# dimmer_for_poor.net
KiCad netlist of a schematic drawn in EAGLE
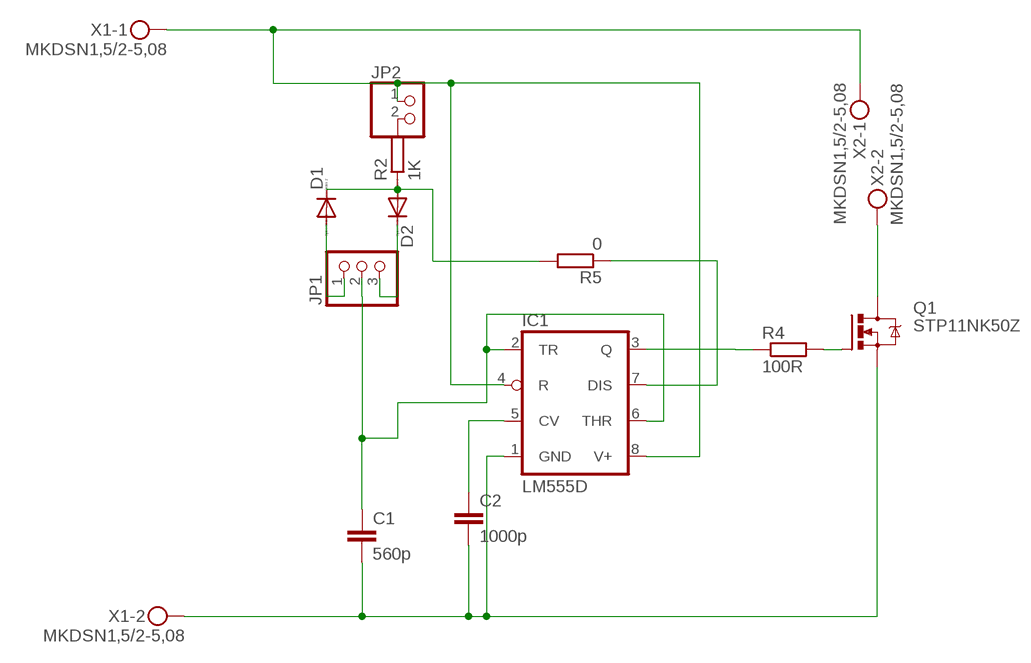
[diagram p0: schematic, sheet 1]

(export (version "E")
  (design (tool "Eeschema 10.0.6"))
  (components
    (comp (ref "C1")
      (value "560p")
      (footprint "eagle-import:C0805")
      (libsource (lib "eagle-import") (part "C-EUC0805"))
    )
    (comp (ref "C2")
      (value "1000p")
      (footprint "eagle-import:C1206")
      (libsource (lib "eagle-import") (part "C-EUC1206"))
    )
    (comp (ref "D1")
      (value "DIODE-MINIMELF")
      (footprint "eagle-import:MINIMELF")
      (libsource (lib "eagle-import") (part "DIODE-MINIMELF"))
    )
    (comp (ref "D2")
      (value "DIODE-MINIMELF")
      (footprint "eagle-import:MINIMELF")
      (libsource (lib "eagle-import") (part "DIODE-MINIMELF"))
    )
    (comp (ref "IC1")
      (value "LM555D")
      (footprint "eagle-import:SO08")
      (libsource (lib "eagle-import") (part "555DLM"))
    )
    (comp (ref "JP1")
      (value "PINHD-1X3/90")
      (footprint "eagle-import:1X03_90")
      (libsource (lib "eagle-import") (part "PINHD-1X3/90"))
    )
    (comp (ref "JP2")
      (value "PINHD-1X2")
      (footprint "eagle-import:1X02")
      (libsource (lib "eagle-import") (part "PINHD-1X2"))
    )
    (comp (ref "Q1")
      (value "STP11NK50Z")
      (footprint "eagle-import:TO220BV")
      (libsource (lib "eagle-import") (part "IRF740"))
    )
    (comp (ref "R2")
      (value "1K")
      (footprint "eagle-import:R0603")
      (libsource (lib "eagle-import") (part "R-EU_R0603"))
    )
    (comp (ref "R4")
      (value "100R")
      (footprint "eagle-import:R1206")
      (libsource (lib "eagle-import") (part "R-EU_R1206"))
    )
    (comp (ref "R5")
      (value "0")
      (footprint "eagle-import:R1206")
      (libsource (lib "eagle-import") (part "R-EU_R1206"))
    )
    (comp (ref "X1")
      (value "MKDSN1,5/2-5,08")
      (footprint "eagle-import:MKDSN1,5_2-5,08")
      (libsource (lib "eagle-import") (part "MKDSN1,5/2-5,08"))
    )
    (comp (ref "X2")
      (value "MKDSN1,5/2-5,08")
      (footprint "eagle-import:MKDSN1,5_2-5,08")
      (libsource (lib "eagle-import") (part "MKDSN1,5/2-5,08"))
    )
  )
  (nets
    (net (code "1") (name "Net-(D1-PadA)") (class "Default")
      (node (ref "D1") (pin "A") (pinfunction "A_A") (pintype "passive"))
      (node (ref "JP1") (pin "1") (pinfunction "1_1") (pintype "passive"))
    )
    (net (code "2") (name "Net-(D1-PadC)") (class "Default")
      (node (ref "D1") (pin "C") (pinfunction "C_C") (pintype "passive"))
      (node (ref "D2") (pin "A") (pinfunction "A_A") (pintype "passive"))
      (node (ref "R2") (pin "1") (pinfunction "1_1") (pintype "passive"))
      (node (ref "R5") (pin "2") (pinfunction "2_2") (pintype "passive"))
    )
    (net (code "3") (name "Net-(D2-PadC)") (class "Default")
      (node (ref "D2") (pin "C") (pinfunction "C_C") (pintype "passive"))
      (node (ref "JP1") (pin "3") (pinfunction "3_3") (pintype "passive"))
    )
    (net (code "4") (name "Net-(IC1-CV)") (class "Default")
      (node (ref "C2") (pin "1") (pinfunction "1_1") (pintype "passive"))
      (node (ref "IC1") (pin "5") (pinfunction "CV_5") (pintype "input"))
    )
    (net (code "5") (name "Net-(IC1-DIS)") (class "Default")
      (node (ref "IC1") (pin "7") (pinfunction "DIS_7") (pintype "input"))
      (node (ref "R5") (pin "1") (pinfunction "1_1") (pintype "passive"))
    )
    (net (code "6") (name "Net-(IC1-GND)") (class "Default")
      (node (ref "C1") (pin "2") (pinfunction "2_2") (pintype "passive"))
      (node (ref "C2") (pin "2") (pinfunction "2_2") (pintype "passive"))
      (node (ref "IC1") (pin "1") (pinfunction "GND_1") (pintype "power_in"))
      (node (ref "Q1") (pin "S") (pinfunction "S_S") (pintype "passive"))
      (node (ref "X1") (pin "2") (pinfunction "KL_2") (pintype "passive"))
    )
    (net (code "7") (name "Net-(IC1-Q)") (class "Default")
      (node (ref "IC1") (pin "3") (pinfunction "Q_3") (pintype "output"))
      (node (ref "R4") (pin "1") (pinfunction "1_1") (pintype "passive"))
    )
    (net (code "8") (name "Net-(IC1-R)") (class "Default")
      (node (ref "IC1") (pin "4") (pinfunction "R_4") (pintype "input"))
      (node (ref "IC1") (pin "8") (pinfunction "V+_8") (pintype "power_in"))
      (node (ref "JP2") (pin "1") (pinfunction "1_1") (pintype "passive"))
      (node (ref "X1") (pin "1") (pinfunction "KL_1") (pintype "passive"))
      (node (ref "X2") (pin "1") (pinfunction "KL_1") (pintype "passive"))
    )
    (net (code "9") (name "Net-(IC1-THR)") (class "Default")
      (node (ref "C1") (pin "1") (pinfunction "1_1") (pintype "passive"))
      (node (ref "IC1") (pin "2") (pinfunction "TR_2") (pintype "input"))
      (node (ref "IC1") (pin "6") (pinfunction "THR_6") (pintype "input"))
      (node (ref "JP1") (pin "2") (pinfunction "2_2") (pintype "passive"))
    )
    (net (code "10") (name "Net-(JP2-Pad2)") (class "Default")
      (node (ref "JP2") (pin "2") (pinfunction "2_2") (pintype "passive"))
      (node (ref "R2") (pin "2") (pinfunction "2_2") (pintype "passive"))
    )
    (net (code "11") (name "Net-(Q1-PadG)") (class "Default")
      (node (ref "Q1") (pin "G") (pinfunction "G_G") (pintype "passive"))
      (node (ref "R4") (pin "2") (pinfunction "2_2") (pintype "passive"))
    )
    (net (code "12") (name "Net-(X2B-KL)") (class "Default")
      (node (ref "Q1") (pin "D") (pinfunction "D_D") (pintype "passive"))
      (node (ref "X2") (pin "2") (pinfunction "KL_2") (pintype "passive"))
    )
  )
)
